# Main-avionics-3_5.net
KiCad netlist of a schematic drawn in EAGLE
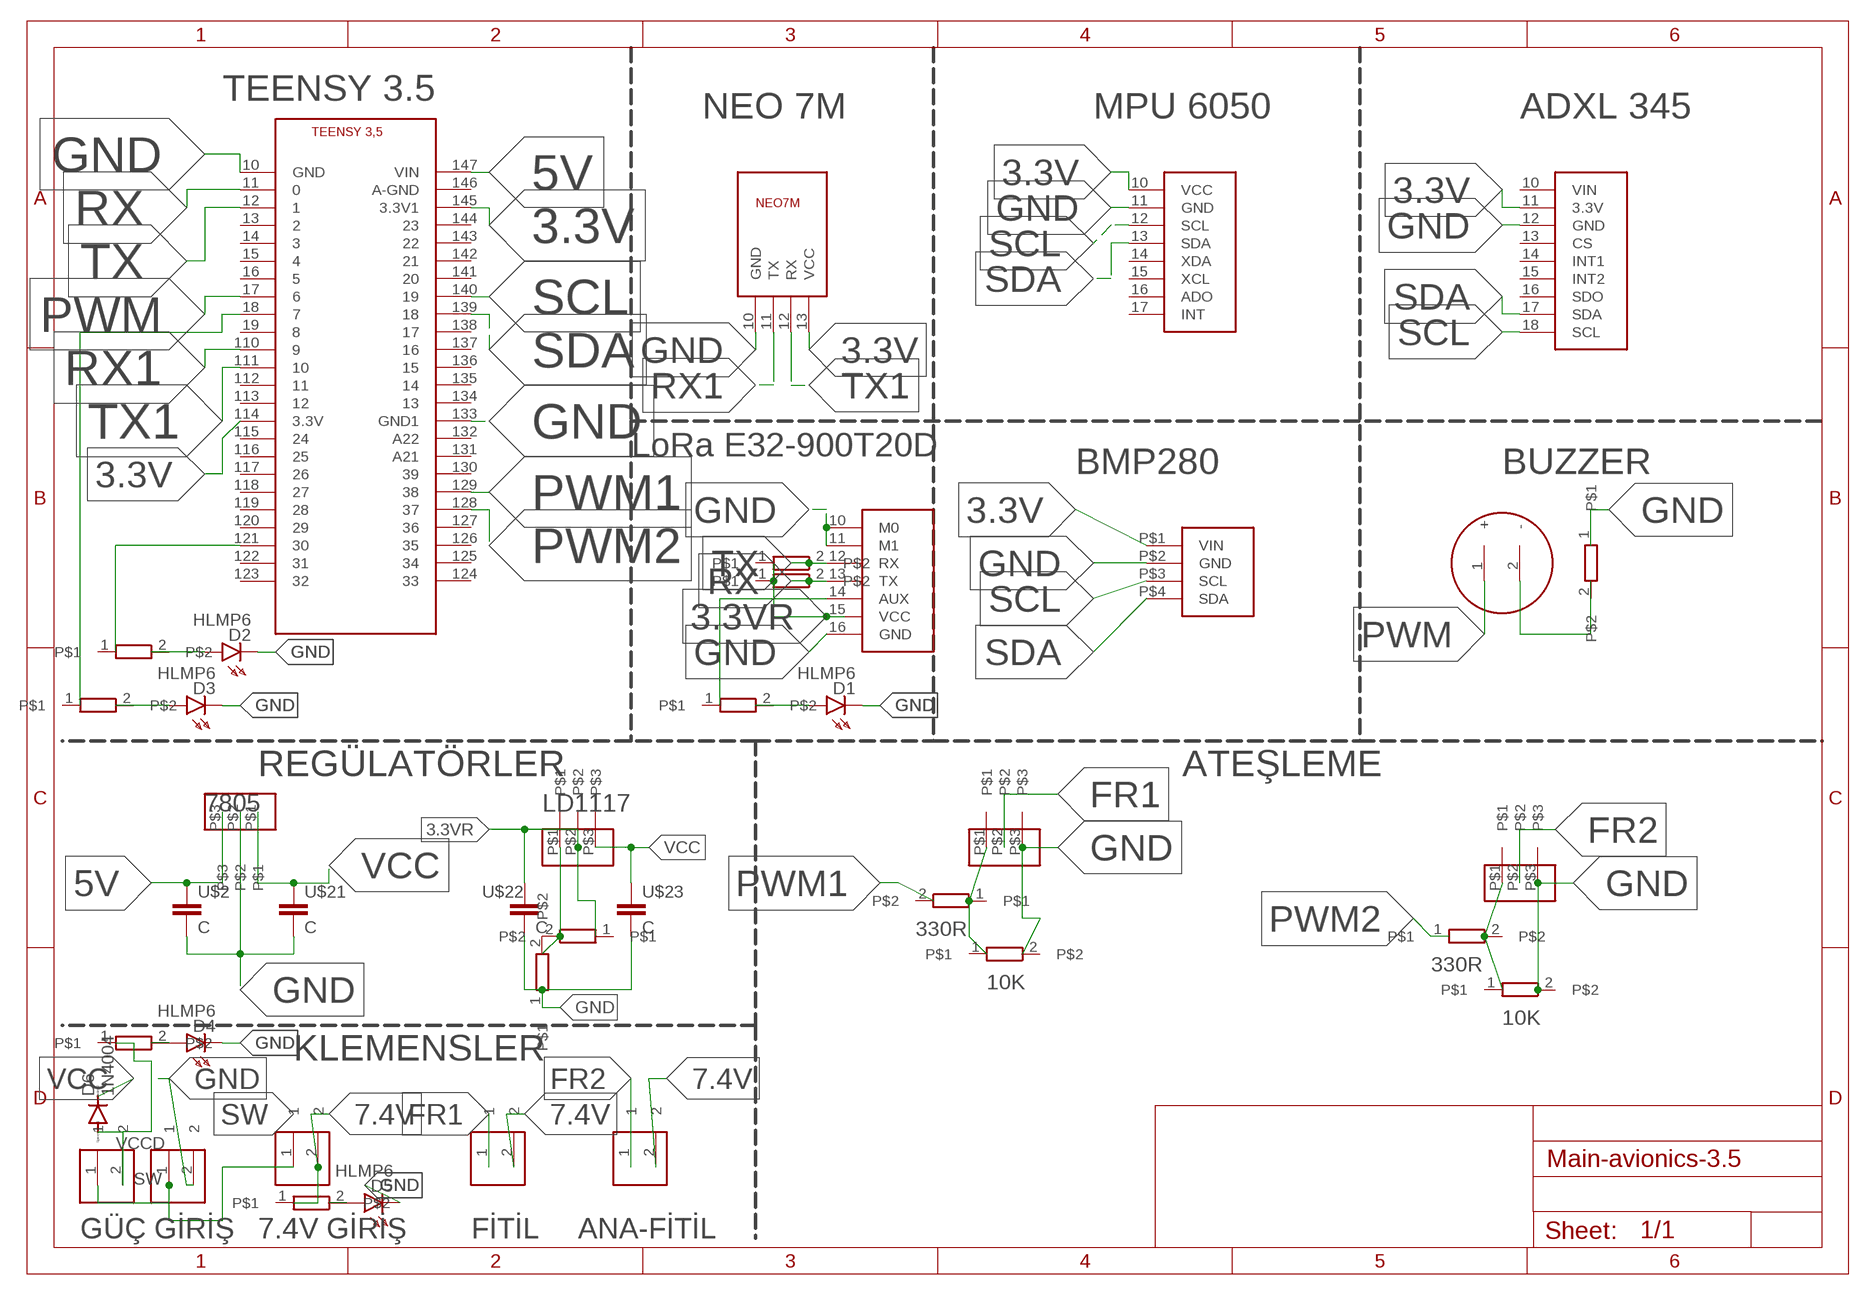
[diagram p0: schematic, sheet 1]

(export (version "E")
  (design (tool "Eeschema 10.0.6"))
  (components
    (comp (ref "1K")
      (value "R")
      (footprint "eagle-import:0204_7")
      (libsource (lib "eagle-import") (part "R"))
    )
    (comp (ref "10R")
      (value "R")
      (footprint "eagle-import:0204_7")
      (libsource (lib "eagle-import") (part "R"))
    )
    (comp (ref "10R1")
      (value "R")
      (footprint "eagle-import:0204_7")
      (libsource (lib "eagle-import") (part "R"))
    )
    (comp (ref "10R2")
      (value "R")
      (footprint "eagle-import:0204_7")
      (libsource (lib "eagle-import") (part "R"))
    )
    (comp (ref "10R3")
      (value "R")
      (footprint "eagle-import:0204_7")
      (libsource (lib "eagle-import") (part "R"))
    )
    (comp (ref "10R4")
      (value "R")
      (footprint "eagle-import:0204_7")
      (libsource (lib "eagle-import") (part "R"))
    )
    (comp (ref "10R5")
      (value "R")
      (footprint "eagle-import:0204_7")
      (libsource (lib "eagle-import") (part "R"))
    )
    (comp (ref "10R6")
      (value "R")
      (footprint "eagle-import:0204_7")
      (libsource (lib "eagle-import") (part "R"))
    )
    (comp (ref "10R7")
      (value "R")
      (footprint "eagle-import:0204_7")
      (libsource (lib "eagle-import") (part "R"))
    )
    (comp (ref "10R8")
      (value "R")
      (footprint "eagle-import:0204_7")
      (libsource (lib "eagle-import") (part "R"))
    )
    (comp (ref "10R9")
      (value "R")
      (footprint "eagle-import:0204_7")
      (libsource (lib "eagle-import") (part "R"))
    )
    (comp (ref "D1")
      (value "HLMP6")
      (footprint "eagle-import:HLMP6")
      (fields (field (name "MF") "AGILENT TECHNOLOGIES") (field (name "MPN") "HLMP-6500"))
      (libsource (lib "eagle-import") (part "HLMP6"))
    )
    (comp (ref "D2")
      (value "HLMP6")
      (footprint "eagle-import:HLMP6")
      (fields (field (name "MF") "AGILENT TECHNOLOGIES") (field (name "MPN") "HLMP-6500"))
      (libsource (lib "eagle-import") (part "HLMP6"))
    )
    (comp (ref "D3")
      (value "HLMP6")
      (footprint "eagle-import:HLMP6")
      (fields (field (name "MF") "AGILENT TECHNOLOGIES") (field (name "MPN") "HLMP-6500"))
      (libsource (lib "eagle-import") (part "HLMP6"))
    )
    (comp (ref "D4")
      (value "HLMP6")
      (footprint "eagle-import:HLMP6")
      (fields (field (name "MF") "AGILENT TECHNOLOGIES") (field (name "MPN") "HLMP-6500"))
      (libsource (lib "eagle-import") (part "HLMP6"))
    )
    (comp (ref "D5")
      (value "HLMP6")
      (footprint "eagle-import:HLMP6")
      (fields (field (name "MF") "AGILENT TECHNOLOGIES") (field (name "MPN") "HLMP-6500"))
      (libsource (lib "eagle-import") (part "HLMP6"))
    )
    (comp (ref "D6")
      (value "1N4004")
      (footprint "eagle-import:DO41-10")
      (libsource (lib "eagle-import") (part "1N4004"))
    )
    (comp (ref "U$1")
      (value "ADXL345")
      (footprint "eagle-import:ADXL345")
      (libsource (lib "eagle-import") (part "ADXL345"))
    )
    (comp (ref "U$2")
      (value "C")
      (footprint "eagle-import:C075-032X103")
      (libsource (lib "eagle-import") (part "C"))
    )
    (comp (ref "U$3")
      (value "BUZZEER")
      (footprint "eagle-import:BUZZER")
      (libsource (lib "eagle-import") (part "BUZZEER"))
    )
    (comp (ref "U$4")
      (value "KLEMENS")
      (footprint "eagle-import:KLEMENS")
      (libsource (lib "eagle-import") (part "KLEMENS"))
    )
    (comp (ref "U$5")
      (value "KLEMENS")
      (footprint "eagle-import:KLEMENS")
      (libsource (lib "eagle-import") (part "KARTYENİ_KLEMENS"))
    )
    (comp (ref "U$6")
      (value "LORA")
      (footprint "eagle-import:LORA")
      (libsource (lib "eagle-import") (part "LORA"))
    )
    (comp (ref "U$7")
      (value "KLEMENS")
      (footprint "eagle-import:KLEMENS")
      (libsource (lib "eagle-import") (part "KLEMENS"))
    )
    (comp (ref "U$8")
      (value "NEO7M")
      (footprint "eagle-import:NEO7M")
      (libsource (lib "eagle-import") (part "NEO7M"))
    )
    (comp (ref "U$9")
      (value "REGULATOR")
      (footprint "eagle-import:REGULATOR")
      (libsource (lib "eagle-import") (part "REGULATOR"))
    )
    (comp (ref "U$11")
      (value "TEENSY")
      (footprint "eagle-import:TEENSY")
      (libsource (lib "eagle-import") (part "TEENSY"))
    )
    (comp (ref "U$13")
      (value "MPU6050")
      (footprint "eagle-import:MPU6050")
      (libsource (lib "eagle-import") (part "MPU6050"))
    )
    (comp (ref "U$14")
      (value "KLEMENS")
      (footprint "eagle-import:KLEMENS")
      (libsource (lib "eagle-import") (part "KLEMENS"))
    )
    (comp (ref "U$15")
      (value "R")
      (footprint "eagle-import:0204_7")
      (libsource (lib "eagle-import") (part "R"))
    )
    (comp (ref "U$16")
      (value "KLEMENS")
      (footprint "eagle-import:KLEMENS")
      (libsource (lib "eagle-import") (part "KARTYENİ_KLEMENS"))
    )
    (comp (ref "U$17")
      (value "R")
      (footprint "eagle-import:0204_7")
      (libsource (lib "eagle-import") (part "R"))
    )
    (comp (ref "U$18")
      (value "R")
      (footprint "eagle-import:0204_7")
      (libsource (lib "eagle-import") (part "R"))
    )
    (comp (ref "U$19")
      (value "REGULATOR")
      (footprint "eagle-import:REGULATOR")
      (libsource (lib "eagle-import") (part "REGULATOR"))
    )
    (comp (ref "U$20")
      (value "BMP280")
      (footprint "eagle-import:BMP280")
      (libsource (lib "eagle-import") (part "BMP280"))
    )
    (comp (ref "U$21")
      (value "C")
      (footprint "eagle-import:C075-032X103")
      (libsource (lib "eagle-import") (part "C"))
    )
    (comp (ref "U$22")
      (value "C")
      (footprint "eagle-import:C075-032X103")
      (libsource (lib "eagle-import") (part "C"))
    )
    (comp (ref "U$23")
      (value "C")
      (footprint "eagle-import:C075-032X103")
      (libsource (lib "eagle-import") (part "C"))
    )
    (comp (ref "U$24")
      (value "REGULATOR")
      (footprint "eagle-import:REGULATOR")
      (libsource (lib "eagle-import") (part "REGULATOR"))
    )
    (comp (ref "U$25")
      (value "REGULATOR")
      (footprint "eagle-import:REGULATOR")
      (libsource (lib "eagle-import") (part "REGULATOR"))
    )
  )
  (nets
    (net (code "1") (name "/VCCD") (class "Default")
      (node (ref "10R8") (pin "1") (pinfunction "P$1_1") (pintype "bidirectional"))
      (node (ref "D6") (pin "A") (pinfunction "A_A") (pintype "passive"))
      (node (ref "U$5") (pin "2") (pinfunction "2_2") (pintype "bidirectional"))
    )
    (net (code "2") (name "3.3V") (class "Default")
      (node (ref "U$1") (pin "11") (pinfunction "3.3V_11") (pintype "bidirectional"))
      (node (ref "U$11") (pin "114") (pinfunction "3.3V_114") (pintype "bidirectional"))
      (node (ref "U$11") (pin "145") (pinfunction "3.3V1_145") (pintype "bidirectional"))
      (node (ref "U$13") (pin "10") (pinfunction "VCC_10") (pintype "bidirectional"))
      (node (ref "U$20") (pin "P$1") (pinfunction "VIN_P$1") (pintype "bidirectional"))
      (node (ref "U$8") (pin "13") (pinfunction "VCC_13") (pintype "bidirectional"))
    )
    (net (code "3") (name "3.3VR") (class "Default")
      (node (ref "10R1") (pin "1") (pinfunction "P$1_1") (pintype "bidirectional"))
      (node (ref "10R2") (pin "1") (pinfunction "P$1_1") (pintype "bidirectional"))
      (node (ref "10R4") (pin "1") (pinfunction "P$1_1") (pintype "bidirectional"))
      (node (ref "U$22") (pin "1") (pinfunction "1_1") (pintype "passive"))
      (node (ref "U$24") (pin "P$2") (pinfunction "P$2_P$2") (pintype "bidirectional"))
      (node (ref "U$6") (pin "15") (pinfunction "VCC_15") (pintype "bidirectional"))
    )
    (net (code "4") (name "5V") (class "Default")
      (node (ref "U$11") (pin "147") (pinfunction "VIN_147") (pintype "bidirectional"))
      (node (ref "U$19") (pin "P$3") (pinfunction "P$3_P$3") (pintype "bidirectional"))
      (node (ref "U$2") (pin "1") (pinfunction "1_1") (pintype "passive"))
    )
    (net (code "5") (name "7.4V") (class "Default")
      (node (ref "10R9") (pin "1") (pinfunction "P$1_1") (pintype "bidirectional"))
      (node (ref "U$14") (pin "2") (pinfunction "2_2") (pintype "bidirectional"))
      (node (ref "U$4") (pin "2") (pinfunction "2_2") (pintype "bidirectional"))
      (node (ref "U$7") (pin "2") (pinfunction "2_2") (pintype "bidirectional"))
    )
    (net (code "6") (name "FR1") (class "Default")
      (node (ref "U$25") (pin "P$2") (pinfunction "P$2_P$2") (pintype "bidirectional"))
      (node (ref "U$4") (pin "1") (pinfunction "1_1") (pintype "bidirectional"))
    )
    (net (code "7") (name "FR2") (class "Default")
      (node (ref "U$7") (pin "1") (pinfunction "1_1") (pintype "bidirectional"))
      (node (ref "U$9") (pin "P$2") (pinfunction "P$2_P$2") (pintype "bidirectional"))
    )
    (net (code "8") (name "GND") (class "Default")
      (node (ref "10R") (pin "2") (pinfunction "P$2_2") (pintype "bidirectional"))
      (node (ref "10R5") (pin "1") (pinfunction "P$1_1") (pintype "bidirectional"))
      (node (ref "D1") (pin "K") (pinfunction "K_K") (pintype "passive"))
      (node (ref "D2") (pin "K") (pinfunction "K_K") (pintype "passive"))
      (node (ref "D3") (pin "K") (pinfunction "K_K") (pintype "passive"))
      (node (ref "D4") (pin "K") (pinfunction "K_K") (pintype "passive"))
      (node (ref "D5") (pin "K") (pinfunction "K_K") (pintype "passive"))
      (node (ref "U$1") (pin "12") (pinfunction "GND_12") (pintype "bidirectional"))
      (node (ref "U$11") (pin "10") (pinfunction "GND_10") (pintype "bidirectional"))
      (node (ref "U$11") (pin "133") (pinfunction "GND1_133") (pintype "bidirectional"))
      (node (ref "U$13") (pin "11") (pinfunction "GND_11") (pintype "bidirectional"))
      (node (ref "U$15") (pin "1") (pinfunction "P$1_1") (pintype "bidirectional"))
      (node (ref "U$16") (pin "2") (pinfunction "2_2") (pintype "bidirectional"))
      (node (ref "U$18") (pin "2") (pinfunction "P$2_2") (pintype "bidirectional"))
      (node (ref "U$19") (pin "P$2") (pinfunction "P$2_P$2") (pintype "bidirectional"))
      (node (ref "U$2") (pin "2") (pinfunction "2_2") (pintype "passive"))
      (node (ref "U$20") (pin "P$2") (pinfunction "GND_P$2") (pintype "bidirectional"))
      (node (ref "U$21") (pin "2") (pinfunction "2_2") (pintype "passive"))
      (node (ref "U$22") (pin "2") (pinfunction "2_2") (pintype "passive"))
      (node (ref "U$23") (pin "2") (pinfunction "2_2") (pintype "passive"))
      (node (ref "U$25") (pin "P$3") (pinfunction "P$3_P$3") (pintype "bidirectional"))
      (node (ref "U$6") (pin "10") (pinfunction "M0_10") (pintype "bidirectional"))
      (node (ref "U$6") (pin "11") (pinfunction "M1_11") (pintype "bidirectional"))
      (node (ref "U$6") (pin "16") (pinfunction "GND_16") (pintype "bidirectional"))
      (node (ref "U$8") (pin "10") (pinfunction "GND_10") (pintype "bidirectional"))
      (node (ref "U$9") (pin "P$3") (pinfunction "P$3_P$3") (pintype "bidirectional"))
    )
    (net (code "9") (name "Net-(10R-P$1)") (class "Default")
      (node (ref "10R") (pin "1") (pinfunction "P$1_1") (pintype "bidirectional"))
      (node (ref "1K") (pin "1") (pinfunction "P$1_1") (pintype "bidirectional"))
      (node (ref "U$25") (pin "P$1") (pinfunction "P$1_P$1") (pintype "bidirectional"))
    )
    (net (code "10") (name "Net-(10R3-P$1)") (class "Default")
      (node (ref "10R3") (pin "1") (pinfunction "P$1_1") (pintype "bidirectional"))
      (node (ref "U$6") (pin "14") (pinfunction "AUX_14") (pintype "bidirectional"))
    )
    (net (code "11") (name "Net-(10R3-P$2)") (class "Default")
      (node (ref "10R3") (pin "2") (pinfunction "P$2_2") (pintype "bidirectional"))
      (node (ref "D1") (pin "A") (pinfunction "A_A") (pintype "passive"))
    )
    (net (code "12") (name "Net-(10R4-P$2)") (class "Default")
      (node (ref "10R4") (pin "2") (pinfunction "P$2_2") (pintype "bidirectional"))
      (node (ref "10R5") (pin "2") (pinfunction "P$2_2") (pintype "bidirectional"))
      (node (ref "U$24") (pin "P$1") (pinfunction "P$1_P$1") (pintype "bidirectional"))
    )
    (net (code "13") (name "Net-(10R6-P$1)") (class "Default")
      (node (ref "10R6") (pin "1") (pinfunction "P$1_1") (pintype "bidirectional"))
      (node (ref "U$11") (pin "121") (pinfunction "30_121") (pintype "bidirectional"))
    )
    (net (code "14") (name "Net-(10R6-P$2)") (class "Default")
      (node (ref "10R6") (pin "2") (pinfunction "P$2_2") (pintype "bidirectional"))
      (node (ref "D2") (pin "A") (pinfunction "A_A") (pintype "passive"))
    )
    (net (code "15") (name "Net-(10R7-P$1)") (class "Default")
      (node (ref "10R7") (pin "1") (pinfunction "P$1_1") (pintype "bidirectional"))
      (node (ref "U$11") (pin "18") (pinfunction "7_18") (pintype "bidirectional"))
    )
    (net (code "16") (name "Net-(10R7-P$2)") (class "Default")
      (node (ref "10R7") (pin "2") (pinfunction "P$2_2") (pintype "bidirectional"))
      (node (ref "D3") (pin "A") (pinfunction "A_A") (pintype "passive"))
    )
    (net (code "17") (name "Net-(10R8-P$2)") (class "Default")
      (node (ref "10R8") (pin "2") (pinfunction "P$2_2") (pintype "bidirectional"))
      (node (ref "D4") (pin "A") (pinfunction "A_A") (pintype "passive"))
    )
    (net (code "18") (name "Net-(10R9-P$2)") (class "Default")
      (node (ref "10R9") (pin "2") (pinfunction "P$2_2") (pintype "bidirectional"))
      (node (ref "D5") (pin "A") (pinfunction "A_A") (pintype "passive"))
    )
    (net (code "19") (name "Net-(U$15-P$2)") (class "Default")
      (node (ref "U$15") (pin "2") (pinfunction "P$2_2") (pintype "bidirectional"))
      (node (ref "U$3") (pin "2") (pinfunction "-_2") (pintype "bidirectional"))
    )
    (net (code "20") (name "Net-(U$17-P$2)") (class "Default")
      (node (ref "U$17") (pin "2") (pinfunction "P$2_2") (pintype "bidirectional"))
      (node (ref "U$18") (pin "1") (pinfunction "P$1_1") (pintype "bidirectional"))
      (node (ref "U$9") (pin "P$1") (pinfunction "P$1_P$1") (pintype "bidirectional"))
    )
    (net (code "21") (name "PWM") (class "Default")
      (node (ref "U$11") (pin "17") (pinfunction "6_17") (pintype "bidirectional"))
      (node (ref "U$3") (pin "1") (pinfunction "+_1") (pintype "bidirectional"))
    )
    (net (code "22") (name "PWM1") (class "Default")
      (node (ref "1K") (pin "2") (pinfunction "P$2_2") (pintype "bidirectional"))
      (node (ref "U$11") (pin "129") (pinfunction "38_129") (pintype "bidirectional"))
    )
    (net (code "23") (name "PWM2") (class "Default")
      (node (ref "U$11") (pin "128") (pinfunction "37_128") (pintype "bidirectional"))
      (node (ref "U$17") (pin "1") (pinfunction "P$1_1") (pintype "bidirectional"))
    )
    (net (code "24") (name "RX") (class "Default")
      (node (ref "10R2") (pin "2") (pinfunction "P$2_2") (pintype "bidirectional"))
      (node (ref "U$11") (pin "11") (pinfunction "0_11") (pintype "bidirectional"))
      (node (ref "U$6") (pin "13") (pinfunction "TX_13") (pintype "bidirectional"))
    )
    (net (code "25") (name "RX1") (class "Default")
      (node (ref "U$11") (pin "110") (pinfunction "9_110") (pintype "bidirectional"))
      (node (ref "U$8") (pin "11") (pinfunction "TX_11") (pintype "bidirectional"))
    )
    (net (code "26") (name "SCL") (class "Default")
      (node (ref "U$1") (pin "18") (pinfunction "SCL_18") (pintype "bidirectional"))
      (node (ref "U$11") (pin "140") (pinfunction "19_140") (pintype "bidirectional"))
      (node (ref "U$13") (pin "12") (pinfunction "SCL_12") (pintype "bidirectional"))
      (node (ref "U$20") (pin "P$3") (pinfunction "SCL_P$3") (pintype "bidirectional"))
    )
    (net (code "27") (name "SDA") (class "Default")
      (node (ref "U$1") (pin "17") (pinfunction "SDA_17") (pintype "bidirectional"))
      (node (ref "U$11") (pin "139") (pinfunction "18_139") (pintype "bidirectional"))
      (node (ref "U$13") (pin "13") (pinfunction "SDA_13") (pintype "bidirectional"))
      (node (ref "U$20") (pin "P$4") (pinfunction "SDA_P$4") (pintype "bidirectional"))
    )
    (net (code "28") (name "SW") (class "Default")
      (node (ref "U$14") (pin "1") (pinfunction "1_1") (pintype "bidirectional"))
      (node (ref "U$16") (pin "1") (pinfunction "1_1") (pintype "bidirectional"))
      (node (ref "U$5") (pin "1") (pinfunction "1_1") (pintype "bidirectional"))
    )
    (net (code "29") (name "TX") (class "Default")
      (node (ref "10R1") (pin "2") (pinfunction "P$2_2") (pintype "bidirectional"))
      (node (ref "U$11") (pin "12") (pinfunction "1_12") (pintype "bidirectional"))
      (node (ref "U$6") (pin "12") (pinfunction "RX_12") (pintype "bidirectional"))
    )
    (net (code "30") (name "TX1") (class "Default")
      (node (ref "U$11") (pin "111") (pinfunction "10_111") (pintype "bidirectional"))
      (node (ref "U$8") (pin "12") (pinfunction "RX_12") (pintype "bidirectional"))
    )
    (net (code "31") (name "VCC") (class "Default")
      (node (ref "D6") (pin "C") (pinfunction "C_C") (pintype "passive"))
      (node (ref "U$19") (pin "P$1") (pinfunction "P$1_P$1") (pintype "bidirectional"))
      (node (ref "U$21") (pin "1") (pinfunction "1_1") (pintype "passive"))
      (node (ref "U$23") (pin "1") (pinfunction "1_1") (pintype "passive"))
      (node (ref "U$24") (pin "P$3") (pinfunction "P$3_P$3") (pintype "bidirectional"))
    )
    (net (code "32") (name "unconnected-(U$1-CS-Pad13)") (class "Default")
      (node (ref "U$1") (pin "13") (pinfunction "CS_13") (pintype "bidirectional"))
    )
    (net (code "33") (name "unconnected-(U$1-INT1-Pad14)") (class "Default")
      (node (ref "U$1") (pin "14") (pinfunction "INT1_14") (pintype "bidirectional"))
    )
    (net (code "34") (name "unconnected-(U$1-INT2-Pad15)") (class "Default")
      (node (ref "U$1") (pin "15") (pinfunction "INT2_15") (pintype "bidirectional"))
    )
    (net (code "35") (name "unconnected-(U$1-SDO-Pad16)") (class "Default")
      (node (ref "U$1") (pin "16") (pinfunction "SDO_16") (pintype "bidirectional"))
    )
    (net (code "36") (name "unconnected-(U$1-VIN-Pad10)") (class "Default")
      (node (ref "U$1") (pin "10") (pinfunction "VIN_10") (pintype "bidirectional"))
    )
    (net (code "37") (name "unconnected-(U$11-2-Pad13)") (class "Default")
      (node (ref "U$11") (pin "13") (pinfunction "2_13") (pintype "bidirectional"))
    )
    (net (code "38") (name "unconnected-(U$11-3-Pad14)") (class "Default")
      (node (ref "U$11") (pin "14") (pinfunction "3_14") (pintype "bidirectional"))
    )
    (net (code "39") (name "unconnected-(U$11-4-Pad15)") (class "Default")
      (node (ref "U$11") (pin "15") (pinfunction "4_15") (pintype "bidirectional"))
    )
    (net (code "40") (name "unconnected-(U$11-5-Pad16)") (class "Default")
      (node (ref "U$11") (pin "16") (pinfunction "5_16") (pintype "bidirectional"))
    )
    (net (code "41") (name "unconnected-(U$11-8-Pad19)") (class "Default")
      (node (ref "U$11") (pin "19") (pinfunction "8_19") (pintype "bidirectional"))
    )
    (net (code "42") (name "unconnected-(U$11-11-Pad112)") (class "Default")
      (node (ref "U$11") (pin "112") (pinfunction "11_112") (pintype "bidirectional"))
    )
    (net (code "43") (name "unconnected-(U$11-12-Pad113)") (class "Default")
      (node (ref "U$11") (pin "113") (pinfunction "12_113") (pintype "bidirectional"))
    )
    (net (code "44") (name "unconnected-(U$11-13-Pad134)") (class "Default")
      (node (ref "U$11") (pin "134") (pinfunction "13_134") (pintype "bidirectional"))
    )
    (net (code "45") (name "unconnected-(U$11-14-Pad135)") (class "Default")
      (node (ref "U$11") (pin "135") (pinfunction "14_135") (pintype "bidirectional"))
    )
    (net (code "46") (name "unconnected-(U$11-15-Pad136)") (class "Default")
      (node (ref "U$11") (pin "136") (pinfunction "15_136") (pintype "bidirectional"))
    )
    (net (code "47") (name "unconnected-(U$11-16-Pad137)") (class "Default")
      (node (ref "U$11") (pin "137") (pinfunction "16_137") (pintype "bidirectional"))
    )
    (net (code "48") (name "unconnected-(U$11-17-Pad138)") (class "Default")
      (node (ref "U$11") (pin "138") (pinfunction "17_138") (pintype "bidirectional"))
    )
    (net (code "49") (name "unconnected-(U$11-20-Pad141)") (class "Default")
      (node (ref "U$11") (pin "141") (pinfunction "20_141") (pintype "bidirectional"))
    )
    (net (code "50") (name "unconnected-(U$11-21-Pad142)") (class "Default")
      (node (ref "U$11") (pin "142") (pinfunction "21_142") (pintype "bidirectional"))
    )
    (net (code "51") (name "unconnected-(U$11-22-Pad143)") (class "Default")
      (node (ref "U$11") (pin "143") (pinfunction "22_143") (pintype "bidirectional"))
    )
    (net (code "52") (name "unconnected-(U$11-23-Pad144)") (class "Default")
      (node (ref "U$11") (pin "144") (pinfunction "23_144") (pintype "bidirectional"))
    )
    (net (code "53") (name "unconnected-(U$11-24-Pad115)") (class "Default")
      (node (ref "U$11") (pin "115") (pinfunction "24_115") (pintype "bidirectional"))
    )
    (net (code "54") (name "unconnected-(U$11-25-Pad116)") (class "Default")
      (node (ref "U$11") (pin "116") (pinfunction "25_116") (pintype "bidirectional"))
    )
    (net (code "55") (name "unconnected-(U$11-26-Pad117)") (class "Default")
      (node (ref "U$11") (pin "117") (pinfunction "26_117") (pintype "bidirectional"))
    )
    (net (code "56") (name "unconnected-(U$11-27-Pad118)") (class "Default")
      (node (ref "U$11") (pin "118") (pinfunction "27_118") (pintype "bidirectional"))
    )
    (net (code "57") (name "unconnected-(U$11-28-Pad119)") (class "Default")
      (node (ref "U$11") (pin "119") (pinfunction "28_119") (pintype "bidirectional"))
    )
    (net (code "58") (name "unconnected-(U$11-29-Pad120)") (class "Default")
      (node (ref "U$11") (pin "120") (pinfunction "29_120") (pintype "bidirectional"))
    )
    (net (code "59") (name "unconnected-(U$11-31-Pad122)") (class "Default")
      (node (ref "U$11") (pin "122") (pinfunction "31_122") (pintype "bidirectional"))
    )
    (net (code "60") (name "unconnected-(U$11-32-Pad123)") (class "Default")
      (node (ref "U$11") (pin "123") (pinfunction "32_123") (pintype "bidirectional"))
    )
    (net (code "61") (name "unconnected-(U$11-33-Pad124)") (class "Default")
      (node (ref "U$11") (pin "124") (pinfunction "33_124") (pintype "bidirectional"))
    )
    (net (code "62") (name "unconnected-(U$11-34-Pad125)") (class "Default")
      (node (ref "U$11") (pin "125") (pinfunction "34_125") (pintype "bidirectional"))
    )
    (net (code "63") (name "unconnected-(U$11-35-Pad126)") (class "Default")
      (node (ref "U$11") (pin "126") (pinfunction "35_126") (pintype "bidirectional"))
    )
    (net (code "64") (name "unconnected-(U$11-36-Pad127)") (class "Default")
      (node (ref "U$11") (pin "127") (pinfunction "36_127") (pintype "bidirectional"))
    )
    (net (code "65") (name "unconnected-(U$11-39-Pad130)") (class "Default")
      (node (ref "U$11") (pin "130") (pinfunction "39_130") (pintype "bidirectional"))
    )
    (net (code "66") (name "unconnected-(U$11-A-GND-Pad146)") (class "Default")
      (node (ref "U$11") (pin "146") (pinfunction "A-GND_146") (pintype "bidirectional"))
    )
    (net (code "67") (name "unconnected-(U$11-A21-Pad131)") (class "Default")
      (node (ref "U$11") (pin "131") (pinfunction "A21_131") (pintype "bidirectional"))
    )
    (net (code "68") (name "unconnected-(U$11-A22-Pad132)") (class "Default")
      (node (ref "U$11") (pin "132") (pinfunction "A22_132") (pintype "bidirectional"))
    )
    (net (code "69") (name "unconnected-(U$13-ADO-Pad16)") (class "Default")
      (node (ref "U$13") (pin "16") (pinfunction "ADO_16") (pintype "bidirectional"))
    )
    (net (code "70") (name "unconnected-(U$13-INT-Pad17)") (class "Default")
      (node (ref "U$13") (pin "17") (pinfunction "INT_17") (pintype "bidirectional"))
    )
    (net (code "71") (name "unconnected-(U$13-XCL-Pad15)") (class "Default")
      (node (ref "U$13") (pin "15") (pinfunction "XCL_15") (pintype "bidirectional"))
    )
    (net (code "72") (name "unconnected-(U$13-XDA-Pad14)") (class "Default")
      (node (ref "U$13") (pin "14") (pinfunction "XDA_14") (pintype "bidirectional"))
    )
  )
)
